# PATHS_1_2_SMD.net
KiCad netlist of a schematic drawn in EAGLE
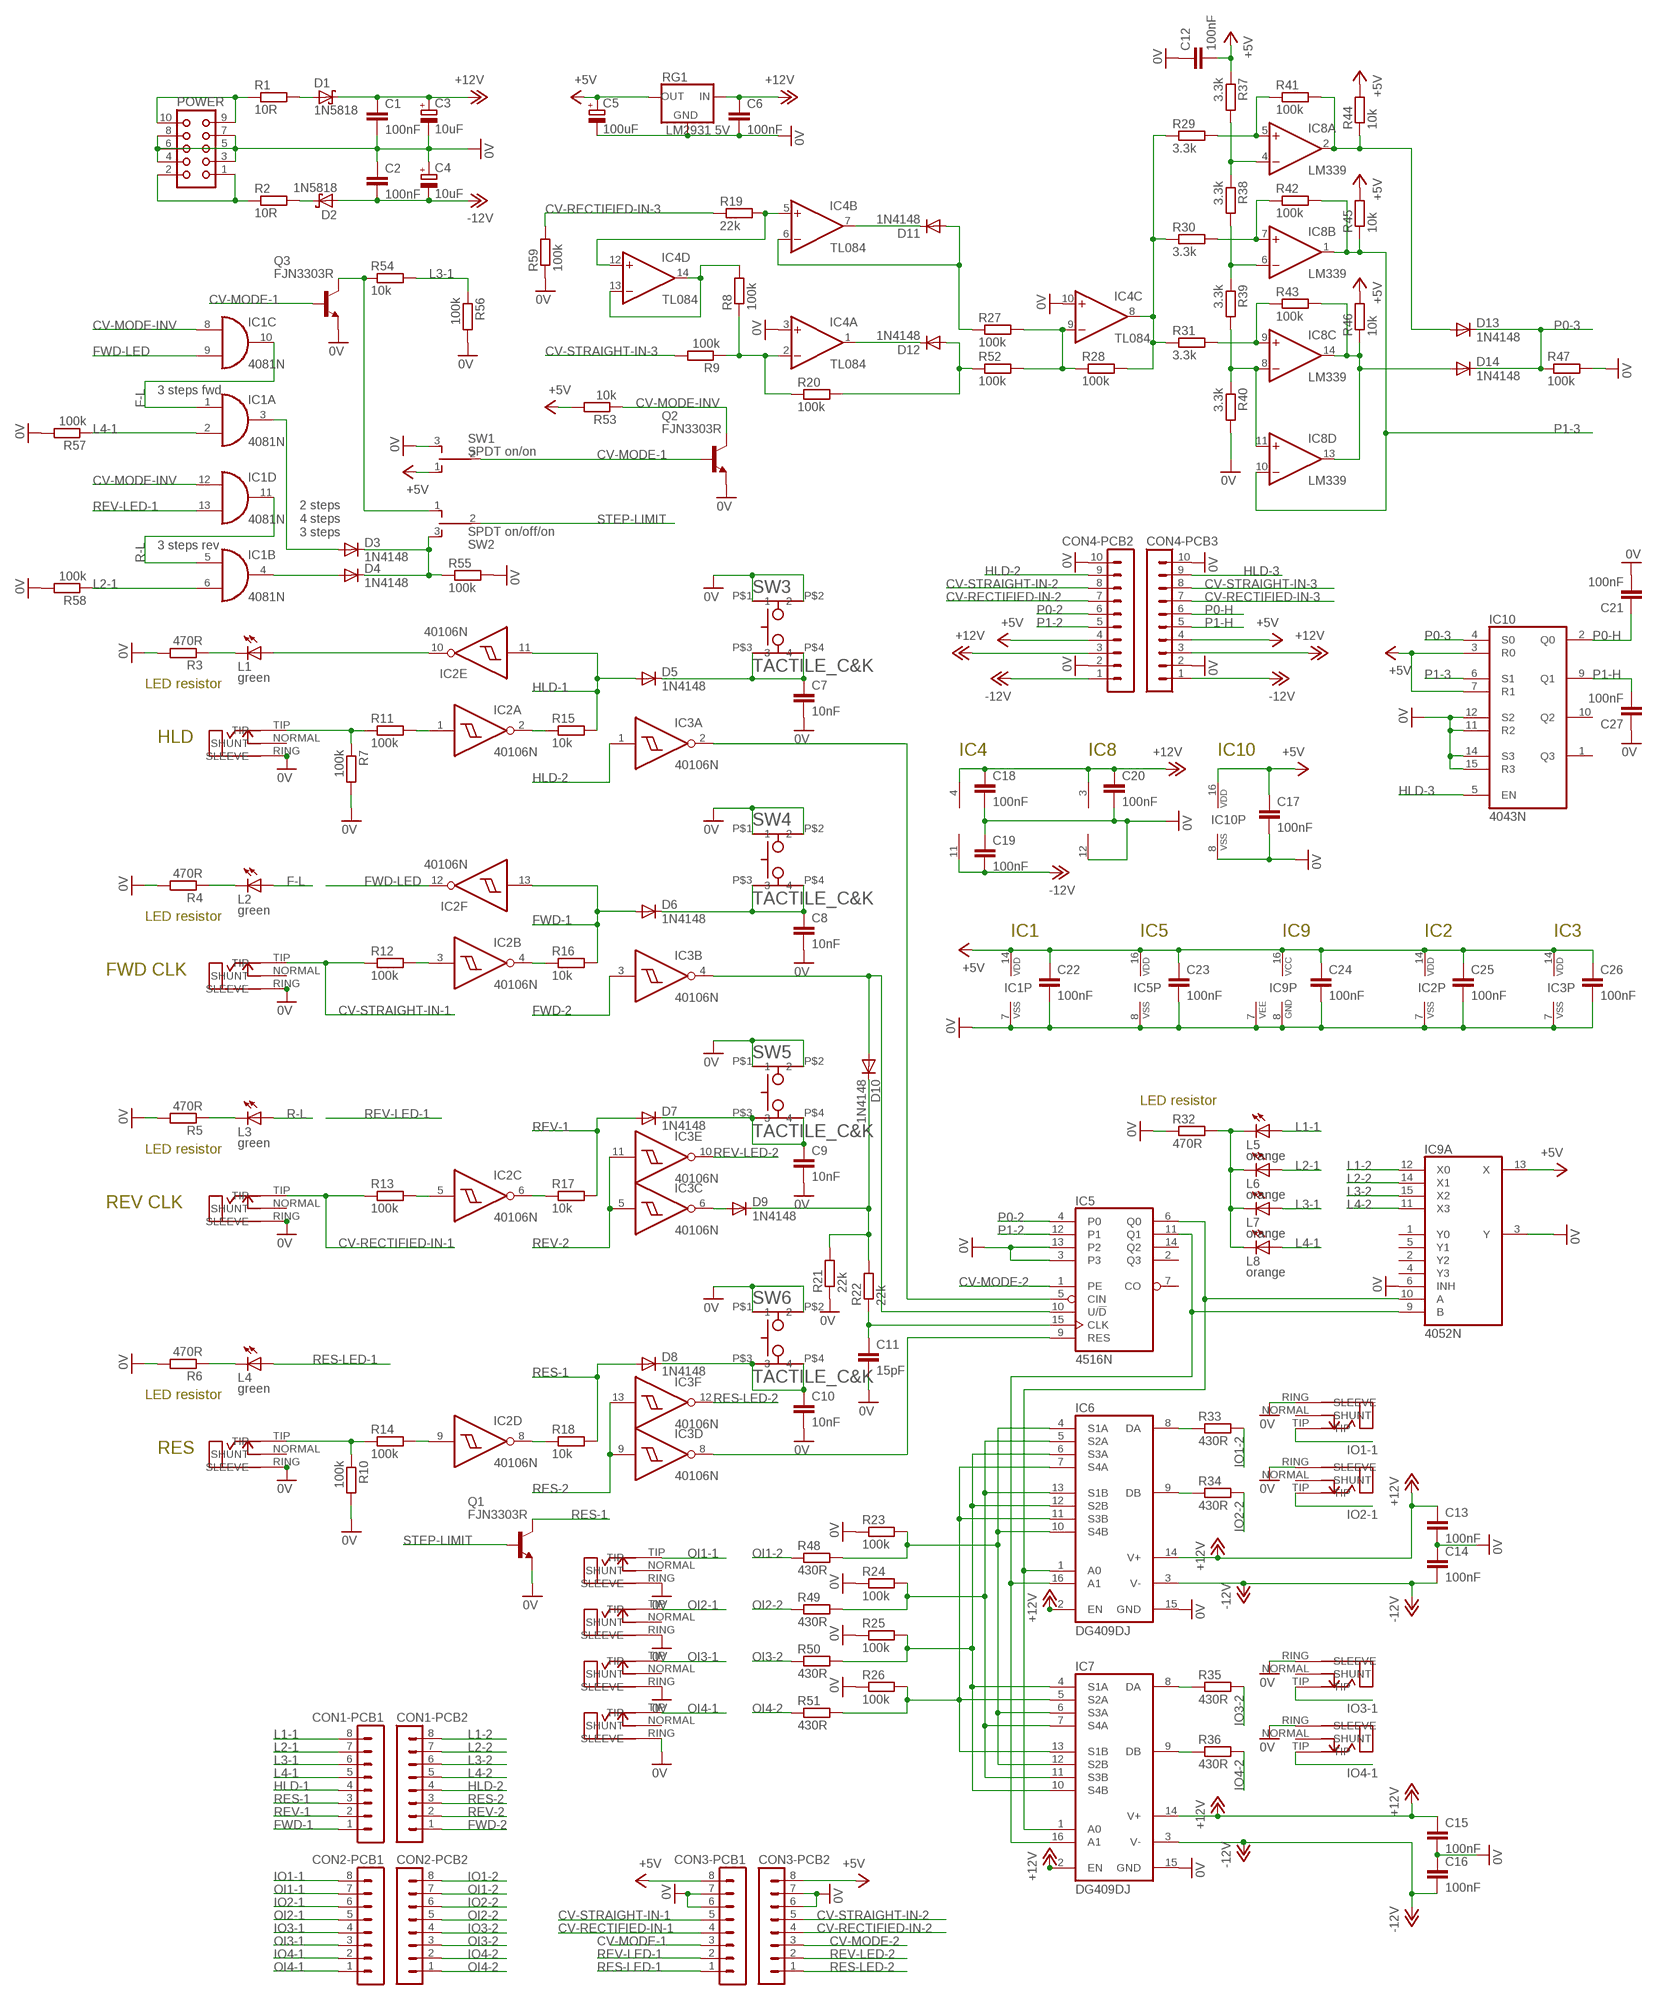
[diagram p0: schematic, sheet 1]

(export (version "E")
  (design (tool "Eeschema 10.0.6"))
  (components
    (comp (ref "C1")
      (value "100nF")
      (footprint "eagle-import:C025-024X044")
      (libsource (lib "eagle-import") (part "C-EU025-024X044"))
    )
    (comp (ref "C2")
      (value "100nF")
      (footprint "eagle-import:C025-024X044")
      (libsource (lib "eagle-import") (part "C-EU025-024X044"))
    )
    (comp (ref "C3")
      (value "10uF")
      (footprint "eagle-import:E2-5")
      (libsource (lib "eagle-import") (part "CPOL-EUE2-5"))
    )
    (comp (ref "C4")
      (value "10uF")
      (footprint "eagle-import:E2-5")
      (libsource (lib "eagle-import") (part "CPOL-EUE2-5"))
    )
    (comp (ref "C5")
      (value "100uF")
      (footprint "eagle-import:E2,5-6")
      (libsource (lib "eagle-import") (part "CPOL-EUE2.5-6"))
    )
    (comp (ref "C6")
      (value "100nF")
      (footprint "eagle-import:C025-024X044")
      (libsource (lib "eagle-import") (part "C-EU025-024X044"))
    )
    (comp (ref "C7")
      (value "10nF")
      (footprint "eagle-import:C025-024X044")
      (libsource (lib "eagle-import") (part "C-EU025-024X044"))
    )
    (comp (ref "C8")
      (value "10nF")
      (footprint "eagle-import:C025-024X044")
      (libsource (lib "eagle-import") (part "C-EU025-024X044"))
    )
    (comp (ref "C9")
      (value "10nF")
      (footprint "eagle-import:C025-024X044")
      (libsource (lib "eagle-import") (part "C-EU025-024X044"))
    )
    (comp (ref "C10")
      (value "10nF")
      (footprint "eagle-import:C025-024X044")
      (libsource (lib "eagle-import") (part "C-EU025-024X044"))
    )
    (comp (ref "C11")
      (value "15pF")
      (footprint "eagle-import:C025-024X044")
      (libsource (lib "eagle-import") (part "C-EU025-024X044"))
    )
    (comp (ref "C12")
      (value "100nF")
      (footprint "eagle-import:C025-024X044")
      (libsource (lib "eagle-import") (part "C-EU025-024X044"))
    )
    (comp (ref "C13")
      (value "100nF")
      (footprint "eagle-import:C025-024X044")
      (libsource (lib "eagle-import") (part "C-EU025-024X044"))
    )
    (comp (ref "C14")
      (value "100nF")
      (footprint "eagle-import:C025-024X044")
      (libsource (lib "eagle-import") (part "C-EU025-024X044"))
    )
    (comp (ref "C15")
      (value "100nF")
      (footprint "eagle-import:C025-024X044")
      (libsource (lib "eagle-import") (part "C-EU025-024X044"))
    )
    (comp (ref "C16")
      (value "100nF")
      (footprint "eagle-import:C025-024X044")
      (libsource (lib "eagle-import") (part "C-EU025-024X044"))
    )
    (comp (ref "C17")
      (value "100nF")
      (footprint "eagle-import:C025-024X044")
      (libsource (lib "eagle-import") (part "C-EU025-024X044"))
    )
    (comp (ref "C18")
      (value "100nF")
      (footprint "eagle-import:C025-024X044")
      (libsource (lib "eagle-import") (part "C-EU025-024X044"))
    )
    (comp (ref "C19")
      (value "100nF")
      (footprint "eagle-import:C025-024X044")
      (libsource (lib "eagle-import") (part "C-EU025-024X044"))
    )
    (comp (ref "C20")
      (value "100nF")
      (footprint "eagle-import:C025-024X044")
      (libsource (lib "eagle-import") (part "C-EU025-024X044"))
    )
    (comp (ref "C21")
      (value "100nF")
      (footprint "eagle-import:C025-024X044")
      (libsource (lib "eagle-import") (part "C-EU025-024X044"))
    )
    (comp (ref "C22")
      (value "100nF")
      (footprint "eagle-import:C025-024X044")
      (libsource (lib "eagle-import") (part "C-EU025-024X044"))
    )
    (comp (ref "C23")
      (value "100nF")
      (footprint "eagle-import:C025-024X044")
      (libsource (lib "eagle-import") (part "C-EU025-024X044"))
    )
    (comp (ref "C24")
      (value "100nF")
      (footprint "eagle-import:C025-024X044")
      (libsource (lib "eagle-import") (part "C-EU025-024X044"))
    )
    (comp (ref "C25")
      (value "100nF")
      (footprint "eagle-import:C025-024X044")
      (libsource (lib "eagle-import") (part "C-EU025-024X044"))
    )
    (comp (ref "C26")
      (value "100nF")
      (footprint "eagle-import:C025-024X044")
      (libsource (lib "eagle-import") (part "C-EU025-024X044"))
    )
    (comp (ref "C27")
      (value "100nF")
      (footprint "eagle-import:C025-024X044")
      (libsource (lib "eagle-import") (part "C-EU025-024X044"))
    )
    (comp (ref "CON1-PCB1")
      (value "MA08-1")
      (footprint "eagle-import:MA08-1")
      (libsource (lib "eagle-import") (part "MA08-1"))
    )
    (comp (ref "CON1-PCB2")
      (value "MA08-1")
      (footprint "eagle-import:MA08-1")
      (libsource (lib "eagle-import") (part "MA08-1"))
    )
    (comp (ref "CON2-PCB1")
      (value "MA08-1")
      (footprint "eagle-import:MA08-1")
      (libsource (lib "eagle-import") (part "MA08-1"))
    )
    (comp (ref "CON2-PCB2")
      (value "MA08-1")
      (footprint "eagle-import:MA08-1")
      (libsource (lib "eagle-import") (part "MA08-1"))
    )
    (comp (ref "CON3-PCB1")
      (value "MA08-1")
      (footprint "eagle-import:MA08-1")
      (libsource (lib "eagle-import") (part "MA08-1"))
    )
    (comp (ref "CON3-PCB2")
      (value "MA08-1")
      (footprint "eagle-import:MA08-1")
      (libsource (lib "eagle-import") (part "MA08-1"))
    )
    (comp (ref "CON4-PCB2")
      (value "MA10-1")
      (footprint "eagle-import:MA10-1")
      (libsource (lib "eagle-import") (part "MA10-1"))
    )
    (comp (ref "CON4-PCB3")
      (value "MA10-1")
      (footprint "eagle-import:MA10-1")
      (libsource (lib "eagle-import") (part "MA10-1"))
    )
    (comp (ref "D1")
      (value "1N5818")
      (footprint "eagle-import:DO41-7")
      (libsource (lib "eagle-import") (part "SB130DO-204AL"))
    )
    (comp (ref "D2")
      (value "1N5818")
      (footprint "eagle-import:DO41-7")
      (libsource (lib "eagle-import") (part "SB130DO-204AL"))
    )
    (comp (ref "D3")
      (value "1N4148")
      (footprint "eagle-import:DO35-6")
      (libsource (lib "eagle-import") (part "1N4148DO35-6"))
    )
    (comp (ref "D4")
      (value "1N4148")
      (footprint "eagle-import:DO35-6")
      (libsource (lib "eagle-import") (part "1N4148DO35-6"))
    )
    (comp (ref "D5")
      (value "1N4148")
      (footprint "eagle-import:DO35-6")
      (libsource (lib "eagle-import") (part "1N4148DO35-6"))
    )
    (comp (ref "D6")
      (value "1N4148")
      (footprint "eagle-import:DO35-6")
      (libsource (lib "eagle-import") (part "1N4148DO35-6"))
    )
    (comp (ref "D7")
      (value "1N4148")
      (footprint "eagle-import:DO35-6")
      (libsource (lib "eagle-import") (part "1N4148DO35-6"))
    )
    (comp (ref "D8")
      (value "1N4148")
      (footprint "eagle-import:DO35-6")
      (libsource (lib "eagle-import") (part "1N4148DO35-6"))
    )
    (comp (ref "D9")
      (value "1N4148")
      (footprint "eagle-import:DO35-6")
      (libsource (lib "eagle-import") (part "1N4148DO35-6"))
    )
    (comp (ref "D10")
      (value "1N4148")
      (footprint "eagle-import:DO35-6")
      (libsource (lib "eagle-import") (part "1N4148DO35-6"))
    )
    (comp (ref "D11")
      (value "1N4148")
      (footprint "eagle-import:DO35-6")
      (libsource (lib "eagle-import") (part "1N4148DO35-6"))
    )
    (comp (ref "D12")
      (value "1N4148")
      (footprint "eagle-import:DO35-6")
      (libsource (lib "eagle-import") (part "1N4148DO35-6"))
    )
    (comp (ref "D13")
      (value "1N4148")
      (footprint "eagle-import:DO35-6")
      (libsource (lib "eagle-import") (part "1N4148DO35-6"))
    )
    (comp (ref "D14")
      (value "1N4148")
      (footprint "eagle-import:DO35-6")
      (libsource (lib "eagle-import") (part "1N4148DO35-6"))
    )
    (comp (ref "FWD")
      (value "ERTHENVAR_3.5MM_JACKINLINE2")
      (footprint "eagle-import:THONKICON-TWISTED")
      (libsource (lib "eagle-import") (part "ERTHENVAR_3.5MM_JACKINLINE2"))
    )
    (comp (ref "HLD")
      (value "ERTHENVAR_3.5MM_JACKINLINE2")
      (footprint "eagle-import:THONKICON-TWISTED")
      (libsource (lib "eagle-import") (part "ERTHENVAR_3.5MM_JACKINLINE2"))
    )
    (comp (ref "I/O1")
      (value "ERTHENVAR_3.5MM_JACKINLINE2")
      (footprint "eagle-import:THONKICON-TWISTED")
      (libsource (lib "eagle-import") (part "ERTHENVAR_3.5MM_JACKINLINE2"))
    )
    (comp (ref "I/O2")
      (value "ERTHENVAR_3.5MM_JACKINLINE2")
      (footprint "eagle-import:THONKICON-TWISTED")
      (libsource (lib "eagle-import") (part "ERTHENVAR_3.5MM_JACKINLINE2"))
    )
    (comp (ref "I/O3")
      (value "ERTHENVAR_3.5MM_JACKINLINE2")
      (footprint "eagle-import:THONKICON-TWISTED")
      (libsource (lib "eagle-import") (part "ERTHENVAR_3.5MM_JACKINLINE2"))
    )
    (comp (ref "I/O4")
      (value "ERTHENVAR_3.5MM_JACKINLINE2")
      (footprint "eagle-import:THONKICON-TWISTED")
      (libsource (lib "eagle-import") (part "ERTHENVAR_3.5MM_JACKINLINE2"))
    )
    (comp (ref "IC1")
      (value "4081N")
      (footprint "eagle-import:DIL14")
      (libsource (lib "eagle-import") (part "4081N"))
    )
    (comp (ref "IC2")
      (value "40106N")
      (footprint "eagle-import:DIL14")
      (libsource (lib "eagle-import") (part "40106N"))
    )
    (comp (ref "IC3")
      (value "40106N")
      (footprint "eagle-import:DIL14")
      (libsource (lib "eagle-import") (part "40106N"))
    )
    (comp (ref "IC4")
      (value "TL084")
      (footprint "eagle-import:DIL14")
      (libsource (lib "eagle-import") (part "TL074P"))
    )
    (comp (ref "IC5")
      (value "4516N")
      (footprint "eagle-import:DIL16")
      (libsource (lib "eagle-import") (part "4516N"))
    )
    (comp (ref "IC6")
      (value "DG409DJ")
      (footprint "eagle-import:DIL16")
      (fields (field (name "MF") "INTERSIL"))
      (libsource (lib "eagle-import") (part "DG409DJ"))
    )
    (comp (ref "IC7")
      (value "DG409DJ")
      (footprint "eagle-import:DIL16")
      (fields (field (name "MF") "INTERSIL"))
      (libsource (lib "eagle-import") (part "DG409DJ"))
    )
    (comp (ref "IC8")
      (value "LM339")
      (footprint "eagle-import:DIL14")
      (libsource (lib "eagle-import") (part "LM2901N"))
    )
    (comp (ref "IC9")
      (value "4052N")
      (footprint "eagle-import:DIL16")
      (libsource (lib "eagle-import") (part "4052N"))
    )
    (comp (ref "IC10")
      (value "4043N")
      (footprint "eagle-import:DIL16")
      (libsource (lib "eagle-import") (part "4043N"))
    )
    (comp (ref "L1")
      (value "green")
      (footprint "eagle-import:LED3MM")
      (libsource (lib "eagle-import") (part "LED3MM"))
    )
    (comp (ref "L2")
      (value "green")
      (footprint "eagle-import:LED3MM")
      (libsource (lib "eagle-import") (part "LED3MM"))
    )
    (comp (ref "L3")
      (value "green")
      (footprint "eagle-import:LED3MM")
      (libsource (lib "eagle-import") (part "LED3MM"))
    )
    (comp (ref "L4")
      (value "green")
      (footprint "eagle-import:LED3MM")
      (libsource (lib "eagle-import") (part "LED3MM"))
    )
    (comp (ref "L5")
      (value "orange")
      (footprint "eagle-import:LED3MM")
      (libsource (lib "eagle-import") (part "LED3MM"))
    )
    (comp (ref "L6")
      (value "orange")
      (footprint "eagle-import:LED3MM")
      (libsource (lib "eagle-import") (part "LED3MM"))
    )
    (comp (ref "L7")
      (value "orange")
      (footprint "eagle-import:LED3MM")
      (libsource (lib "eagle-import") (part "LED3MM"))
    )
    (comp (ref "L8")
      (value "orange")
      (footprint "eagle-import:LED3MM")
      (libsource (lib "eagle-import") (part "LED3MM"))
    )
    (comp (ref "O/I1")
      (value "ERTHENVAR_3.5MM_JACKINLINE2")
      (footprint "eagle-import:THONKICON-TWISTED")
      (libsource (lib "eagle-import") (part "ERTHENVAR_3.5MM_JACKINLINE2"))
    )
    (comp (ref "O/I2")
      (value "ERTHENVAR_3.5MM_JACKINLINE2")
      (footprint "eagle-import:THONKICON-TWISTED")
      (libsource (lib "eagle-import") (part "ERTHENVAR_3.5MM_JACKINLINE2"))
    )
    (comp (ref "O/I3")
      (value "ERTHENVAR_3.5MM_JACKINLINE2")
      (footprint "eagle-import:THONKICON-TWISTED")
      (libsource (lib "eagle-import") (part "ERTHENVAR_3.5MM_JACKINLINE2"))
    )
    (comp (ref "O/I4")
      (value "ERTHENVAR_3.5MM_JACKINLINE2")
      (footprint "eagle-import:THONKICON-TWISTED")
      (libsource (lib "eagle-import") (part "ERTHENVAR_3.5MM_JACKINLINE2"))
    )
    (comp (ref "POWER")
      (value "CON10L")
      (footprint "eagle-import:CON10L")
      (libsource (lib "eagle-import") (part "CON10L"))
    )
    (comp (ref "Q1")
      (value "FJN3303R")
      (footprint "eagle-import:TO92-LINE")
      (libsource (lib "eagle-import") (part "FJN3303R"))
    )
    (comp (ref "Q2")
      (value "FJN3303R")
      (footprint "eagle-import:TO92-LINE")
      (libsource (lib "eagle-import") (part "FJN3303R"))
    )
    (comp (ref "Q3")
      (value "FJN3303R")
      (footprint "eagle-import:TO92-LINE")
      (libsource (lib "eagle-import") (part "FJN3303R"))
    )
    (comp (ref "R1")
      (value "10R")
      (footprint "eagle-import:0207_9")
      (libsource (lib "eagle-import") (part "R-EU_0207/10"))
    )
    (comp (ref "R2")
      (value "10R")
      (footprint "eagle-import:0207_9")
      (libsource (lib "eagle-import") (part "R-EU_0207/10"))
    )
    (comp (ref "R3")
      (value "470R")
      (footprint "eagle-import:0204_5")
      (libsource (lib "eagle-import") (part "R-EU_0204/5"))
    )
    (comp (ref "R4")
      (value "470R")
      (footprint "eagle-import:0204_5")
      (libsource (lib "eagle-import") (part "R-EU_0204/5"))
    )
    (comp (ref "R5")
      (value "470R")
      (footprint "eagle-import:0204_5")
      (libsource (lib "eagle-import") (part "R-EU_0204/5"))
    )
    (comp (ref "R6")
      (value "470R")
      (footprint "eagle-import:0204_5")
      (libsource (lib "eagle-import") (part "R-EU_0204/5"))
    )
    (comp (ref "R7")
      (value "100k")
      (footprint "eagle-import:0204_5")
      (libsource (lib "eagle-import") (part "R-EU_0204/5"))
    )
    (comp (ref "R8")
      (value "100k")
      (footprint "eagle-import:0204_5")
      (libsource (lib "eagle-import") (part "R-EU_0204/5"))
    )
    (comp (ref "R9")
      (value "100k")
      (footprint "eagle-import:0204_5")
      (libsource (lib "eagle-import") (part "R-EU_0204/5"))
    )
    (comp (ref "R10")
      (value "100k")
      (footprint "eagle-import:0204_5")
      (libsource (lib "eagle-import") (part "R-EU_0204/5"))
    )
    (comp (ref "R11")
      (value "100k")
      (footprint "eagle-import:0204_5")
      (libsource (lib "eagle-import") (part "R-EU_0204/5"))
    )
    (comp (ref "R12")
      (value "100k")
      (footprint "eagle-import:0204_5")
      (libsource (lib "eagle-import") (part "R-EU_0204/5"))
    )
    (comp (ref "R13")
      (value "100k")
      (footprint "eagle-import:0204_5")
      (libsource (lib "eagle-import") (part "R-EU_0204/5"))
    )
    (comp (ref "R14")
      (value "100k")
      (footprint "eagle-import:0204_5")
      (libsource (lib "eagle-import") (part "R-EU_0204/5"))
    )
    (comp (ref "R15")
      (value "10k")
      (footprint "eagle-import:0204_5")
      (libsource (lib "eagle-import") (part "R-EU_0204/5"))
    )
    (comp (ref "R16")
      (value "10k")
      (footprint "eagle-import:0204_5")
      (libsource (lib "eagle-import") (part "R-EU_0204/5"))
    )
    (comp (ref "R17")
      (value "10k")
      (footprint "eagle-import:0204_5")
      (libsource (lib "eagle-import") (part "R-EU_0204/5"))
    )
    (comp (ref "R18")
      (value "10k")
      (footprint "eagle-import:0204_5")
      (libsource (lib "eagle-import") (part "R-EU_0204/5"))
    )
    (comp (ref "R19")
      (value "22k")
      (footprint "eagle-import:0204_5")
      (libsource (lib "eagle-import") (part "R-EU_0204/5"))
    )
    (comp (ref "R20")
      (value "100k")
      (footprint "eagle-import:0204_5")
      (libsource (lib "eagle-import") (part "R-EU_0204/5"))
    )
    (comp (ref "R21")
      (value "22k")
      (footprint "eagle-import:0204_5")
      (libsource (lib "eagle-import") (part "R-EU_0204/5"))
    )
    (comp (ref "R22")
      (value "22k")
      (footprint "eagle-import:0204_5")
      (libsource (lib "eagle-import") (part "R-EU_0204/5"))
    )
    (comp (ref "R23")
      (value "100k")
      (footprint "eagle-import:0204_5")
      (libsource (lib "eagle-import") (part "R-EU_0204/5"))
    )
    (comp (ref "R24")
      (value "100k")
      (footprint "eagle-import:0204_5")
      (libsource (lib "eagle-import") (part "R-EU_0204/5"))
    )
    (comp (ref "R25")
      (value "100k")
      (footprint "eagle-import:0204_5")
      (libsource (lib "eagle-import") (part "R-EU_0204/5"))
    )
    (comp (ref "R26")
      (value "100k")
      (footprint "eagle-import:0204_5")
      (libsource (lib "eagle-import") (part "R-EU_0204/5"))
    )
    (comp (ref "R27")
      (value "100k")
      (footprint "eagle-import:0204_5")
      (libsource (lib "eagle-import") (part "R-EU_0204/5"))
    )
    (comp (ref "R28")
      (value "100k")
      (footprint "eagle-import:0204_5")
      (libsource (lib "eagle-import") (part "R-EU_0204/5"))
    )
    (comp (ref "R29")
      (value "3.3k")
      (footprint "eagle-import:0204_5")
      (libsource (lib "eagle-import") (part "R-EU_0204/5"))
    )
    (comp (ref "R30")
      (value "3.3k")
      (footprint "eagle-import:0204_5")
      (libsource (lib "eagle-import") (part "R-EU_0204/5"))
    )
    (comp (ref "R31")
      (value "3.3k")
      (footprint "eagle-import:0204_5")
      (libsource (lib "eagle-import") (part "R-EU_0204/5"))
    )
    (comp (ref "R32")
      (value "470R")
      (footprint "eagle-import:0204_5")
      (libsource (lib "eagle-import") (part "R-EU_0204/5"))
    )
    (comp (ref "R33")
      (value "430R")
      (footprint "eagle-import:0207_9")
      (libsource (lib "eagle-import") (part "R-EU_0207/10"))
    )
    (comp (ref "R34")
      (value "430R")
      (footprint "eagle-import:0207_9")
      (libsource (lib "eagle-import") (part "R-EU_0207/10"))
    )
    (comp (ref "R35")
      (value "430R")
      (footprint "eagle-import:0207_9")
      (libsource (lib "eagle-import") (part "R-EU_0207/10"))
    )
    (comp (ref "R36")
      (value "430R")
      (footprint "eagle-import:0207_9")
      (libsource (lib "eagle-import") (part "R-EU_0207/10"))
    )
    (comp (ref "R37")
      (value "3.3k")
      (footprint "eagle-import:0204_5")
      (libsource (lib "eagle-import") (part "R-EU_0204/5"))
    )
    (comp (ref "R38")
      (value "3.3k")
      (footprint "eagle-import:0204_5")
      (libsource (lib "eagle-import") (part "R-EU_0204/5"))
    )
    (comp (ref "R39")
      (value "3.3k")
      (footprint "eagle-import:0204_5")
      (libsource (lib "eagle-import") (part "R-EU_0204/5"))
    )
    (comp (ref "R40")
      (value "3.3k")
      (footprint "eagle-import:0204_5")
      (libsource (lib "eagle-import") (part "R-EU_0204/5"))
    )
    (comp (ref "R41")
      (value "100k")
      (footprint "eagle-import:0204_5")
      (libsource (lib "eagle-import") (part "R-EU_0204/5"))
    )
    (comp (ref "R42")
      (value "100k")
      (footprint "eagle-import:0204_5")
      (libsource (lib "eagle-import") (part "R-EU_0204/5"))
    )
    (comp (ref "R43")
      (value "100k")
      (footprint "eagle-import:0204_5")
      (libsource (lib "eagle-import") (part "R-EU_0204/5"))
    )
    (comp (ref "R44")
      (value "10k")
      (footprint "eagle-import:0204_5")
      (libsource (lib "eagle-import") (part "R-EU_0204/5"))
    )
    (comp (ref "R45")
      (value "10k")
      (footprint "eagle-import:0204_5")
      (libsource (lib "eagle-import") (part "R-EU_0204/5"))
    )
    (comp (ref "R46")
      (value "10k")
      (footprint "eagle-import:0204_5")
      (libsource (lib "eagle-import") (part "R-EU_0204/5"))
    )
    (comp (ref "R47")
      (value "100k")
      (footprint "eagle-import:0204_5")
      (libsource (lib "eagle-import") (part "R-EU_0204/5"))
    )
    (comp (ref "R48")
      (value "430R")
      (footprint "eagle-import:0207_9")
      (libsource (lib "eagle-import") (part "R-EU_0207/10"))
    )
    (comp (ref "R49")
      (value "430R")
      (footprint "eagle-import:0207_9")
      (libsource (lib "eagle-import") (part "R-EU_0207/10"))
    )
    (comp (ref "R50")
      (value "430R")
      (footprint "eagle-import:0207_9")
      (libsource (lib "eagle-import") (part "R-EU_0207/10"))
    )
    (comp (ref "R51")
      (value "430R")
      (footprint "eagle-import:0207_9")
      (libsource (lib "eagle-import") (part "R-EU_0207/10"))
    )
    (comp (ref "R52")
      (value "100k")
      (footprint "eagle-import:0204_5")
      (libsource (lib "eagle-import") (part "R-EU_0204/5"))
    )
    (comp (ref "R53")
      (value "10k")
      (footprint "eagle-import:0204_5")
      (libsource (lib "eagle-import") (part "R-EU_0204/5"))
    )
    (comp (ref "R54")
      (value "10k")
      (footprint "eagle-import:0204_5")
      (libsource (lib "eagle-import") (part "R-EU_0204/5"))
    )
    (comp (ref "R55")
      (value "100k")
      (footprint "eagle-import:0204_5")
      (libsource (lib "eagle-import") (part "R-EU_0204/5"))
    )
    (comp (ref "R56")
      (value "100k")
      (footprint "eagle-import:0204_5")
      (libsource (lib "eagle-import") (part "R-EU_0204/5"))
    )
    (comp (ref "R57")
      (value "100k")
      (footprint "eagle-import:0204_5")
      (libsource (lib "eagle-import") (part "R-EU_0204/5"))
    )
    (comp (ref "R58")
      (value "100k")
      (footprint "eagle-import:0204_5")
      (libsource (lib "eagle-import") (part "R-EU_0204/5"))
    )
    (comp (ref "R59")
      (value "100k")
      (footprint "eagle-import:0204_5")
      (libsource (lib "eagle-import") (part "R-EU_0204/5"))
    )
    (comp (ref "RES")
      (value "ERTHENVAR_3.5MM_JACKINLINE2")
      (footprint "eagle-import:THONKICON-TWISTED")
      (libsource (lib "eagle-import") (part "ERTHENVAR_3.5MM_JACKINLINE2"))
    )
    (comp (ref "REV")
      (value "ERTHENVAR_3.5MM_JACKINLINE2")
      (footprint "eagle-import:THONKICON-TWISTED")
      (libsource (lib "eagle-import") (part "ERTHENVAR_3.5MM_JACKINLINE2"))
    )
    (comp (ref "RG1")
      (value "LM2931 5V")
      (footprint "eagle-import:TO92-LINE")
      (libsource (lib "eagle-import") (part "78LXXLM2931XXX"))
    )
    (comp (ref "SW1")
      (value "SPDT on/on")
      (footprint "eagle-import:SPDT-HORIZONTAL-TOP-SUBMINI-MULTICOMP")
      (libsource (lib "eagle-import") (part "SPDTTOP-SUBMINI"))
    )
    (comp (ref "SW2")
      (value "SPDT on/off/on")
      (footprint "eagle-import:SPDT-HORIZONTAL-TOP-SUBMINI-MULTICOMP")
      (libsource (lib "eagle-import") (part "SPDTTOP-SUBMINI"))
    )
    (comp (ref "SW3")
      (value "TACTILE_C&K")
      (footprint "eagle-import:TACTILE_CK")
      (libsource (lib "eagle-import") (part "TACTILE_C&K"))
    )
    (comp (ref "SW4")
      (value "TACTILE_C&K")
      (footprint "eagle-import:TACTILE_CK")
      (libsource (lib "eagle-import") (part "TACTILE_C&K"))
    )
    (comp (ref "SW5")
      (value "TACTILE_C&K")
      (footprint "eagle-import:TACTILE_CK")
      (libsource (lib "eagle-import") (part "TACTILE_C&K"))
    )
    (comp (ref "SW6")
      (value "TACTILE_C&K")
      (footprint "eagle-import:TACTILE_CK")
      (libsource (lib "eagle-import") (part "TACTILE_C&K"))
    )
  )
  (nets
    (net (code "1") (name "+5V") (class "Default")
      (node (ref "C12") (pin "2") (pinfunction "2_2") (pintype "passive"))
      (node (ref "C17") (pin "1") (pinfunction "1_1") (pintype "passive"))
      (node (ref "C22") (pin "1") (pinfunction "1_1") (pintype "passive"))
      (node (ref "C23") (pin "1") (pinfunction "1_1") (pintype "passive"))
      (node (ref "C24") (pin "1") (pinfunction "1_1") (pintype "passive"))
      (node (ref "C25") (pin "1") (pinfunction "1_1") (pintype "passive"))
      (node (ref "C26") (pin "1") (pinfunction "1_1") (pintype "passive"))
      (node (ref "C5") (pin "+") (pinfunction "+_+") (pintype "passive"))
      (node (ref "CON3-PCB1") (pin "8") (pinfunction "8_8") (pintype "passive"))
      (node (ref "CON3-PCB2") (pin "8") (pinfunction "8_8") (pintype "passive"))
      (node (ref "CON4-PCB2") (pin "4") (pinfunction "4_4") (pintype "passive"))
      (node (ref "CON4-PCB3") (pin "4") (pinfunction "4_4") (pintype "passive"))
      (node (ref "IC1") (pin "14") (pinfunction "VDD_14") (pintype "power_in"))
      (node (ref "IC10") (pin "16") (pinfunction "VDD_16") (pintype "power_in"))
      (node (ref "IC10") (pin "3") (pinfunction "R0_3") (pintype "input"))
      (node (ref "IC10") (pin "7") (pinfunction "R1_7") (pintype "input"))
      (node (ref "IC2") (pin "14") (pinfunction "VDD_14") (pintype "power_in"))
      (node (ref "IC3") (pin "14") (pinfunction "VDD_14") (pintype "power_in"))
      (node (ref "IC5") (pin "16") (pinfunction "VDD_16") (pintype "power_in"))
      (node (ref "IC9") (pin "13") (pinfunction "X_13") (pintype "bidirectional"))
      (node (ref "IC9") (pin "16") (pinfunction "VCC_16") (pintype "power_in"))
      (node (ref "R37") (pin "1") (pinfunction "1_1") (pintype "passive"))
      (node (ref "R44") (pin "2") (pinfunction "2_2") (pintype "passive"))
      (node (ref "R45") (pin "2") (pinfunction "2_2") (pintype "passive"))
      (node (ref "R46") (pin "2") (pinfunction "2_2") (pintype "passive"))
      (node (ref "R53") (pin "2") (pinfunction "2_2") (pintype "passive"))
      (node (ref "RG1") (pin "3") (pinfunction "OUT_3") (pintype "passive"))
      (node (ref "SW1") (pin "1") (pinfunction "1_1") (pintype "passive"))
    )
    (net (code "2") (name "+12V") (class "Default")
      (node (ref "C1") (pin "1") (pinfunction "1_1") (pintype "passive"))
      (node (ref "C13") (pin "1") (pinfunction "1_1") (pintype "passive"))
      (node (ref "C15") (pin "1") (pinfunction "1_1") (pintype "passive"))
      (node (ref "C18") (pin "1") (pinfunction "1_1") (pintype "passive"))
      (node (ref "C20") (pin "1") (pinfunction "1_1") (pintype "passive"))
      (node (ref "C3") (pin "+") (pinfunction "+_+") (pintype "passive"))
      (node (ref "C6") (pin "1") (pinfunction "1_1") (pintype "passive"))
      (node (ref "CON4-PCB2") (pin "3") (pinfunction "3_3") (pintype "passive"))
      (node (ref "CON4-PCB3") (pin "3") (pinfunction "3_3") (pintype "passive"))
      (node (ref "D1") (pin "C") (pinfunction "C_C") (pintype "passive"))
      (node (ref "IC4") (pin "4") (pinfunction "V+_4") (pintype "power_in"))
      (node (ref "IC6") (pin "14") (pinfunction "V+_14") (pintype "power_in"))
      (node (ref "IC6") (pin "2") (pinfunction "EN_2") (pintype "input"))
      (node (ref "IC7") (pin "14") (pinfunction "V+_14") (pintype "power_in"))
      (node (ref "IC7") (pin "2") (pinfunction "EN_2") (pintype "input"))
      (node (ref "IC8") (pin "3") (pinfunction "V+_3") (pintype "power_in"))
      (node (ref "RG1") (pin "1") (pinfunction "IN_1") (pintype "input"))
    )
    (net (code "3") (name "-12V") (class "Default")
      (node (ref "C14") (pin "2") (pinfunction "2_2") (pintype "passive"))
      (node (ref "C16") (pin "2") (pinfunction "2_2") (pintype "passive"))
      (node (ref "C19") (pin "2") (pinfunction "2_2") (pintype "passive"))
      (node (ref "C2") (pin "2") (pinfunction "2_2") (pintype "passive"))
      (node (ref "C4") (pin "-") (pinfunction "-_-") (pintype "passive"))
      (node (ref "CON4-PCB2") (pin "1") (pinfunction "1_1") (pintype "passive"))
      (node (ref "CON4-PCB3") (pin "1") (pinfunction "1_1") (pintype "passive"))
      (node (ref "D2") (pin "A") (pinfunction "A_A") (pintype "passive"))
      (node (ref "IC4") (pin "11") (pinfunction "V-_11") (pintype "power_in"))
      (node (ref "IC6") (pin "3") (pinfunction "V-_3") (pintype "power_in"))
      (node (ref "IC7") (pin "3") (pinfunction "V-_3") (pintype "power_in"))
    )
    (net (code "4") (name "/CV-MODE-1") (class "Default")
      (node (ref "CON3-PCB1") (pin "3") (pinfunction "3_3") (pintype "passive"))
      (node (ref "Q2") (pin "1") (pinfunction "B_1") (pintype "passive"))
      (node (ref "Q3") (pin "1") (pinfunction "B_1") (pintype "passive"))
      (node (ref "SW1") (pin "2") (pinfunction "2_2") (pintype "passive"))
    )
    (net (code "5") (name "/CV-MODE-2") (class "Default")
      (node (ref "CON3-PCB2") (pin "3") (pinfunction "3_3") (pintype "passive"))
      (node (ref "IC5") (pin "1") (pinfunction "PE_1") (pintype "input"))
    )
    (net (code "6") (name "/CV-MODE-INV") (class "Default")
      (node (ref "IC1") (pin "12") (pinfunction "I0_12") (pintype "input"))
      (node (ref "IC1") (pin "8") (pinfunction "I0_8") (pintype "input"))
      (node (ref "Q2") (pin "2") (pinfunction "C_2") (pintype "passive"))
      (node (ref "R53") (pin "1") (pinfunction "1_1") (pintype "passive"))
    )
    (net (code "7") (name "/CV-RECTIFIED-IN-1") (class "Default")
      (node (ref "CON3-PCB1") (pin "4") (pinfunction "4_4") (pintype "passive"))
      (node (ref "R13") (pin "1") (pinfunction "1_1") (pintype "passive"))
      (node (ref "REV") (pin "TIP") (pinfunction "TIP_TIP") (pintype "bidirectional"))
    )
    (net (code "8") (name "/CV-RECTIFIED-IN-2") (class "Default")
      (node (ref "CON3-PCB2") (pin "4") (pinfunction "4_4") (pintype "passive"))
      (node (ref "CON4-PCB2") (pin "7") (pinfunction "7_7") (pintype "passive"))
    )
    (net (code "9") (name "/CV-RECTIFIED-IN-3") (class "Default")
      (node (ref "CON4-PCB3") (pin "7") (pinfunction "7_7") (pintype "passive"))
      (node (ref "R19") (pin "1") (pinfunction "1_1") (pintype "passive"))
      (node (ref "R59") (pin "2") (pinfunction "2_2") (pintype "passive"))
    )
    (net (code "10") (name "/CV-STRAIGHT-IN-1") (class "Default")
      (node (ref "CON3-PCB1") (pin "5") (pinfunction "5_5") (pintype "passive"))
      (node (ref "FWD") (pin "TIP") (pinfunction "TIP_TIP") (pintype "bidirectional"))
      (node (ref "R12") (pin "1") (pinfunction "1_1") (pintype "passive"))
    )
    (net (code "11") (name "/CV-STRAIGHT-IN-2") (class "Default")
      (node (ref "CON3-PCB2") (pin "5") (pinfunction "5_5") (pintype "passive"))
      (node (ref "CON4-PCB2") (pin "8") (pinfunction "8_8") (pintype "passive"))
    )
    (net (code "12") (name "/CV-STRAIGHT-IN-3") (class "Default")
      (node (ref "CON4-PCB3") (pin "8") (pinfunction "8_8") (pintype "passive"))
      (node (ref "R9") (pin "2") (pinfunction "2_2") (pintype "passive"))
    )
    (net (code "13") (name "/F-L") (class "Default")
      (node (ref "IC1") (pin "1") (pinfunction "I0_1") (pintype "input"))
      (node (ref "IC1") (pin "10") (pinfunction "O_10") (pintype "output"))
      (node (ref "L2") (pin "A") (pinfunction "A_A") (pintype "passive"))
    )
    (net (code "14") (name "/FWD-1") (class "Default")
      (node (ref "CON1-PCB1") (pin "1") (pinfunction "1_1") (pintype "passive"))
      (node (ref "D6") (pin "ANODE") (pinfunction "A_ANODE") (pintype "passive"))
      (node (ref "IC2") (pin "13") (pinfunction "I_13") (pintype "input"))
      (node (ref "R16") (pin "2") (pinfunction "2_2") (pintype "passive"))
    )
    (net (code "15") (name "/FWD-2") (class "Default")
      (node (ref "CON1-PCB2") (pin "1") (pinfunction "1_1") (pintype "passive"))
      (node (ref "IC3") (pin "3") (pinfunction "I_3") (pintype "input"))
    )
    (net (code "16") (name "/FWD-LED") (class "Default")
      (node (ref "IC1") (pin "9") (pinfunction "I1_9") (pintype "input"))
      (node (ref "IC2") (pin "12") (pinfunction "O_12") (pintype "output"))
    )
    (net (code "17") (name "/HLD-1") (class "Default")
      (node (ref "CON1-PCB1") (pin "4") (pinfunction "4_4") (pintype "passive"))
      (node (ref "D5") (pin "ANODE") (pinfunction "A_ANODE") (pintype "passive"))
      (node (ref "IC2") (pin "11") (pinfunction "I_11") (pintype "input"))
      (node (ref "R15") (pin "2") (pinfunction "2_2") (pintype "passive"))
    )
    (net (code "18") (name "/HLD-2") (class "Default")
      (node (ref "CON1-PCB2") (pin "4") (pinfunction "4_4") (pintype "passive"))
      (node (ref "CON4-PCB2") (pin "9") (pinfunction "9_9") (pintype "passive"))
      (node (ref "IC3") (pin "1") (pinfunction "I_1") (pintype "input"))
    )
    (net (code "19") (name "/HLD-3") (class "Default")
      (node (ref "CON4-PCB3") (pin "9") (pinfunction "9_9") (pintype "passive"))
      (node (ref "IC10") (pin "5") (pinfunction "EN_5") (pintype "input"))
    )
    (net (code "20") (name "/IO1-1") (class "Default")
      (node (ref "CON2-PCB1") (pin "8") (pinfunction "8_8") (pintype "passive"))
      (node (ref "I/O1") (pin "TIP") (pinfunction "TIP_TIP") (pintype "bidirectional"))
    )
    (net (code "21") (name "/IO1-2") (class "Default")
      (node (ref "CON2-PCB2") (pin "8") (pinfunction "8_8") (pintype "passive"))
      (node (ref "R33") (pin "2") (pinfunction "2_2") (pintype "passive"))
    )
    (net (code "22") (name "/IO2-1") (class "Default")
      (node (ref "CON2-PCB1") (pin "6") (pinfunction "6_6") (pintype "passive"))
      (node (ref "I/O2") (pin "TIP") (pinfunction "TIP_TIP") (pintype "bidirectional"))
    )
    (net (code "23") (name "/IO2-2") (class "Default")
      (node (ref "CON2-PCB2") (pin "6") (pinfunction "6_6") (pintype "passive"))
      (node (ref "R34") (pin "2") (pinfunction "2_2") (pintype "passive"))
    )
    (net (code "24") (name "/IO3-1") (class "Default")
      (node (ref "CON2-PCB1") (pin "4") (pinfunction "4_4") (pintype "passive"))
      (node (ref "I/O3") (pin "TIP") (pinfunction "TIP_TIP") (pintype "bidirectional"))
    )
    (net (code "25") (name "/IO3-2") (class "Default")
      (node (ref "CON2-PCB2") (pin "4") (pinfunction "4_4") (pintype "passive"))
      (node (ref "R35") (pin "2") (pinfunction "2_2") (pintype "passive"))
    )
    (net (code "26") (name "/IO4-1") (class "Default")
      (node (ref "CON2-PCB1") (pin "2") (pinfunction "2_2") (pintype "passive"))
      (node (ref "I/O4") (pin "TIP") (pinfunction "TIP_TIP") (pintype "bidirectional"))
    )
    (net (code "27") (name "/IO4-2") (class "Default")
      (node (ref "CON2-PCB2") (pin "2") (pinfunction "2_2") (pintype "passive"))
      (node (ref "R36") (pin "2") (pinfunction "2_2") (pintype "passive"))
    )
    (net (code "28") (name "/L1-1") (class "Default")
      (node (ref "CON1-PCB1") (pin "8") (pinfunction "8_8") (pintype "passive"))
      (node (ref "L5") (pin "A") (pinfunction "A_A") (pintype "passive"))
    )
    (net (code "29") (name "/L1-2") (class "Default")
      (node (ref "CON1-PCB2") (pin "8") (pinfunction "8_8") (pintype "passive"))
      (node (ref "IC9") (pin "12") (pinfunction "X0_12") (pintype "bidirectional"))
    )
    (net (code "30") (name "/L2-1") (class "Default")
      (node (ref "CON1-PCB1") (pin "7") (pinfunction "7_7") (pintype "passive"))
      (node (ref "IC1") (pin "6") (pinfunction "I1_6") (pintype "input"))
      (node (ref "L6") (pin "A") (pinfunction "A_A") (pintype "passive"))
      (node (ref "R58") (pin "1") (pinfunction "1_1") (pintype "passive"))
    )
    (net (code "31") (name "/L2-2") (class "Default")
      (node (ref "CON1-PCB2") (pin "7") (pinfunction "7_7") (pintype "passive"))
      (node (ref "IC9") (pin "14") (pinfunction "X1_14") (pintype "bidirectional"))
    )
    (net (code "32") (name "/L3-1") (class "Default")
      (node (ref "CON1-PCB1") (pin "6") (pinfunction "6_6") (pintype "passive"))
      (node (ref "L7") (pin "A") (pinfunction "A_A") (pintype "passive"))
      (node (ref "R54") (pin "2") (pinfunction "2_2") (pintype "passive"))
      (node (ref "R56") (pin "1") (pinfunction "1_1") (pintype "passive"))
    )
    (net (code "33") (name "/L3-2") (class "Default")
      (node (ref "CON1-PCB2") (pin "6") (pinfunction "6_6") (pintype "passive"))
      (node (ref "IC9") (pin "15") (pinfunction "X2_15") (pintype "bidirectional"))
    )
    (net (code "34") (name "/L4-1") (class "Default")
      (node (ref "CON1-PCB1") (pin "5") (pinfunction "5_5") (pintype "passive"))
      (node (ref "IC1") (pin "2") (pinfunction "I1_2") (pintype "input"))
      (node (ref "L8") (pin "A") (pinfunction "A_A") (pintype "passive"))
      (node (ref "R57") (pin "1") (pinfunction "1_1") (pintype "passive"))
    )
    (net (code "35") (name "/L4-2") (class "Default")
      (node (ref "CON1-PCB2") (pin "5") (pinfunction "5_5") (pintype "passive"))
      (node (ref "IC9") (pin "11") (pinfunction "X3_11") (pintype "bidirectional"))
    )
    (net (code "36") (name "/OI1-1") (class "Default")
      (node (ref "CON2-PCB1") (pin "7") (pinfunction "7_7") (pintype "passive"))
      (node (ref "O/I1") (pin "TIP") (pinfunction "TIP_TIP") (pintype "bidirectional"))
    )
    (net (code "37") (name "/OI1-2") (class "Default")
      (node (ref "CON2-PCB2") (pin "7") (pinfunction "7_7") (pintype "passive"))
      (node (ref "R48") (pin "1") (pinfunction "1_1") (pintype "passive"))
    )
    (net (code "38") (name "/OI2-1") (class "Default")
      (node (ref "CON2-PCB1") (pin "5") (pinfunction "5_5") (pintype "passive"))
      (node (ref "O/I2") (pin "TIP") (pinfunction "TIP_TIP") (pintype "bidirectional"))
    )
    (net (code "39") (name "/OI2-2") (class "Default")
      (node (ref "CON2-PCB2") (pin "5") (pinfunction "5_5") (pintype "passive"))
      (node (ref "R49") (pin "1") (pinfunction "1_1") (pintype "passive"))
    )
    (net (code "40") (name "/OI3-1") (class "Default")
      (node (ref "CON2-PCB1") (pin "3") (pinfunction "3_3") (pintype "passive"))
      (node (ref "O/I3") (pin "TIP") (pinfunction "TIP_TIP") (pintype "bidirectional"))
    )
    (net (code "41") (name "/OI3-2") (class "Default")
      (node (ref "CON2-PCB2") (pin "3") (pinfunction "3_3") (pintype "passive"))
      (node (ref "R50") (pin "1") (pinfunction "1_1") (pintype "passive"))
    )
    (net (code "42") (name "/OI4-1") (class "Default")
      (node (ref "CON2-PCB1") (pin "1") (pinfunction "1_1") (pintype "passive"))
      (node (ref "O/I4") (pin "TIP") (pinfunction "TIP_TIP") (pintype "bidirectional"))
    )
    (net (code "43") (name "/OI4-2") (class "Default")
      (node (ref "CON2-PCB2") (pin "1") (pinfunction "1_1") (pintype "passive"))
      (node (ref "R51") (pin "1") (pinfunction "1_1") (pintype "passive"))
    )
    (net (code "44") (name "/P0-2") (class "Default")
      (node (ref "CON4-PCB2") (pin "6") (pinfunction "6_6") (pintype "passive"))
      (node (ref "IC5") (pin "4") (pinfunction "P0_4") (pintype "input"))
    )
    (net (code "45") (name "/P0-3") (class "Default")
      (node (ref "D13") (pin "CATHODE") (pinfunction "C_CATHODE") (pintype "passive"))
      (node (ref "D14") (pin "CATHODE") (pinfunction "C_CATHODE") (pintype "passive"))
      (node (ref "IC10") (pin "4") (pinfunction "S0_4") (pintype "input"))
      (node (ref "R47") (pin "1") (pinfunction "1_1") (pintype "passive"))
    )
    (net (code "46") (name "/P0-H") (class "Default")
      (node (ref "C21") (pin "1") (pinfunction "1_1") (pintype "passive"))
      (node (ref "CON4-PCB3") (pin "6") (pinfunction "6_6") (pintype "passive"))
      (node (ref "IC10") (pin "2") (pinfunction "Q0_2") (pintype "output"))
    )
    (net (code "47") (name "/P1-2") (class "Default")
      (node (ref "CON4-PCB2") (pin "5") (pinfunction "5_5") (pintype "passive"))
      (node (ref "IC5") (pin "12") (pinfunction "P1_12") (pintype "input"))
    )
    (net (code "48") (name "/P1-3") (class "Default")
      (node (ref "IC10") (pin "6") (pinfunction "S1_6") (pintype "input"))
      (node (ref "IC8") (pin "1") (pinfunction "OUT_1") (pintype "output"))
      (node (ref "IC8") (pin "10") (pinfunction "-IN_10") (pintype "input"))
      (node (ref "R42") (pin "2") (pinfunction "2_2") (pintype "passive"))
      (node (ref "R45") (pin "1") (pinfunction "1_1") (pintype "passive"))
    )
    (net (code "49") (name "/P1-H") (class "Default")
      (node (ref "C27") (pin "2") (pinfunction "2_2") (pintype "passive"))
      (node (ref "CON4-PCB3") (pin "5") (pinfunction "5_5") (pintype "passive"))
      (node (ref "IC10") (pin "9") (pinfunction "Q1_9") (pintype "output"))
    )
    (net (code "50") (name "/R-L") (class "Default")
      (node (ref "IC1") (pin "11") (pinfunction "O_11") (pintype "output"))
      (node (ref "IC1") (pin "5") (pinfunction "I0_5") (pintype "input"))
      (node (ref "L3") (pin "A") (pinfunction "A_A") (pintype "passive"))
    )
    (net (code "51") (name "/RES-1") (class "Default")
      (node (ref "CON1-PCB1") (pin "3") (pinfunction "3_3") (pintype "passive"))
      (node (ref "D8") (pin "ANODE") (pinfunction "A_ANODE") (pintype "passive"))
      (node (ref "Q1") (pin "2") (pinfunction "C_2") (pintype "passive"))
      (node (ref "R18") (pin "2") (pinfunction "2_2") (pintype "passive"))
    )
    (net (code "52") (name "/RES-2") (class "Default")
      (node (ref "CON1-PCB2") (pin "3") (pinfunction "3_3") (pintype "passive"))
      (node (ref "IC3") (pin "13") (pinfunction "I_13") (pintype "input"))
      (node (ref "IC3") (pin "9") (pinfunction "I_9") (pintype "input"))
    )
    (net (code "53") (name "/RES-LED-1") (class "Default")
      (node (ref "CON3-PCB1") (pin "1") (pinfunction "1_1") (pintype "passive"))
      (node (ref "L4") (pin "A") (pinfunction "A_A") (pintype "passive"))
    )
    (net (code "54") (name "/RES-LED-2") (class "Default")
      (node (ref "CON3-PCB2") (pin "1") (pinfunction "1_1") (pintype "passive"))
      (node (ref "IC3") (pin "12") (pinfunction "O_12") (pintype "output"))
    )
    (net (code "55") (name "/REV-1") (class "Default")
      (node (ref "CON1-PCB1") (pin "2") (pinfunction "2_2") (pintype "passive"))
      (node (ref "D7") (pin "ANODE") (pinfunction "A_ANODE") (pintype "passive"))
      (node (ref "R17") (pin "2") (pinfunction "2_2") (pintype "passive"))
    )
    (net (code "56") (name "/REV-2") (class "Default")
      (node (ref "CON1-PCB2") (pin "2") (pinfunction "2_2") (pintype "passive"))
      (node (ref "IC3") (pin "11") (pinfunction "I_11") (pintype "input"))
      (node (ref "IC3") (pin "5") (pinfunction "I_5") (pintype "input"))
    )
    (net (code "57") (name "/REV-LED-1") (class "Default")
      (node (ref "CON3-PCB1") (pin "2") (pinfunction "2_2") (pintype "passive"))
      (node (ref "IC1") (pin "13") (pinfunction "I1_13") (pintype "input"))
    )
    (net (code "58") (name "/REV-LED-2") (class "Default")
      (node (ref "CON3-PCB2") (pin "2") (pinfunction "2_2") (pintype "passive"))
      (node (ref "IC3") (pin "10") (pinfunction "O_10") (pintype "output"))
    )
    (net (code "59") (name "/STEP-LIMIT") (class "Default")
      (node (ref "Q1") (pin "1") (pinfunction "B_1") (pintype "passive"))
      (node (ref "SW2") (pin "2") (pinfunction "2_2") (pintype "passive"))
    )
    (net (code "60") (name "0V") (class "Default")
      (node (ref "C1") (pin "2") (pinfunction "2_2") (pintype "passive"))
      (node (ref "C10") (pin "2") (pinfunction "2_2") (pintype "passive"))
      (node (ref "C11") (pin "2") (pinfunction "2_2") (pintype "passive"))
      (node (ref "C12") (pin "1") (pinfunction "1_1") (pintype "passive"))
      (node (ref "C13") (pin "2") (pinfunction "2_2") (pintype "passive"))
      (node (ref "C14") (pin "1") (pinfunction "1_1") (pintype "passive"))
      (node (ref "C15") (pin "2") (pinfunction "2_2") (pintype "passive"))
      (node (ref "C16") (pin "1") (pinfunction "1_1") (pintype "passive"))
      (node (ref "C17") (pin "2") (pinfunction "2_2") (pintype "passive"))
      (node (ref "C18") (pin "2") (pinfunction "2_2") (pintype "passive"))
      (node (ref "C19") (pin "1") (pinfunction "1_1") (pintype "passive"))
      (node (ref "C2") (pin "1") (pinfunction "1_1") (pintype "passive"))
      (node (ref "C20") (pin "2") (pinfunction "2_2") (pintype "passive"))
      (node (ref "C21") (pin "2") (pinfunction "2_2") (pintype "passive"))
      (node (ref "C22") (pin "2") (pinfunction "2_2") (pintype "passive"))
      (node (ref "C23") (pin "2") (pinfunction "2_2") (pintype "passive"))
      (node (ref "C24") (pin "2") (pinfunction "2_2") (pintype "passive"))
      (node (ref "C25") (pin "2") (pinfunction "2_2") (pintype "passive"))
      (node (ref "C26") (pin "2") (pinfunction "2_2") (pintype "passive"))
      (node (ref "C27") (pin "1") (pinfunction "1_1") (pintype "passive"))
      (node (ref "C3") (pin "-") (pinfunction "-_-") (pintype "passive"))
      (node (ref "C4") (pin "+") (pinfunction "+_+") (pintype "passive"))
      (node (ref "C5") (pin "-") (pinfunction "-_-") (pintype "passive"))
      (node (ref "C6") (pin "2") (pinfunction "2_2") (pintype "passive"))
      (node (ref "C7") (pin "2") (pinfunction "2_2") (pintype "passive"))
      (node (ref "C8") (pin "2") (pinfunction "2_2") (pintype "passive"))
      (node (ref "C9") (pin "2") (pinfunction "2_2") (pintype "passive"))
      (node (ref "CON3-PCB1") (pin "6") (pinfunction "6_6") (pintype "passive"))
      (node (ref "CON3-PCB1") (pin "7") (pinfunction "7_7") (pintype "passive"))
      (node (ref "CON3-PCB2") (pin "6") (pinfunction "6_6") (pintype "passive"))
      (node (ref "CON3-PCB2") (pin "7") (pinfunction "7_7") (pintype "passive"))
      (node (ref "CON4-PCB2") (pin "10") (pinfunction "10_10") (pintype "passive"))
      (node (ref "CON4-PCB2") (pin "2") (pinfunction "2_2") (pintype "passive"))
      (node (ref "CON4-PCB3") (pin "10") (pinfunction "10_10") (pintype "passive"))
      (node (ref "CON4-PCB3") (pin "2") (pinfunction "2_2") (pintype "passive"))
      (node (ref "FWD") (pin "RING") (pinfunction "SLEEVE_RING") (pintype "bidirectional"))
      (node (ref "HLD") (pin "RING") (pinfunction "SLEEVE_RING") (pintype "bidirectional"))
      (node (ref "I/O1") (pin "RING") (pinfunction "SLEEVE_RING") (pintype "bidirectional"))
      (node (ref "I/O2") (pin "RING") (pinfunction "SLEEVE_RING") (pintype "bidirectional"))
      (node (ref "I/O3") (pin "RING") (pinfunction "SLEEVE_RING") (pintype "bidirectional"))
      (node (ref "I/O4") (pin "RING") (pinfunction "SLEEVE_RING") (pintype "bidirectional"))
      (node (ref "IC1") (pin "7") (pinfunction "VSS_7") (pintype "power_in"))
      (node (ref "IC10") (pin "11") (pinfunction "R2_11") (pintype "input"))
      (node (ref "IC10") (pin "12") (pinfunction "S2_12") (pintype "input"))
      (node (ref "IC10") (pin "14") (pinfunction "S3_14") (pintype "input"))
      (node (ref "IC10") (pin "15") (pinfunction "R3_15") (pintype "input"))
      (node (ref "IC10") (pin "8") (pinfunction "VSS_8") (pintype "power_in"))
      (node (ref "IC2") (pin "7") (pinfunction "VSS_7") (pintype "power_in"))
      (node (ref "IC3") (pin "7") (pinfunction "VSS_7") (pintype "power_in"))
      (node (ref "IC4") (pin "10") (pinfunction "+IN_10") (pintype "input"))
      (node (ref "IC4") (pin "3") (pinfunction "+IN_3") (pintype "input"))
      (node (ref "IC5") (pin "13") (pinfunction "P2_13") (pintype "input"))
      (node (ref "IC5") (pin "3") (pinfunction "P3_3") (pintype "input"))
      (node (ref "IC5") (pin "8") (pinfunction "VSS_8") (pintype "power_in"))
      (node (ref "IC6") (pin "15") (pinfunction "GND_15") (pintype "power_in"))
      (node (ref "IC7") (pin "15") (pinfunction "GND_15") (pintype "power_in"))
      (node (ref "IC8") (pin "12") (pinfunction "V-_12") (pintype "power_in"))
      (node (ref "IC9") (pin "3") (pinfunction "Y_3") (pintype "bidirectional"))
      (node (ref "IC9") (pin "6") (pinfunction "INH_6") (pintype "input"))
      (node (ref "IC9") (pin "7") (pinfunction "VEE_7") (pintype "power_in"))
      (node (ref "IC9") (pin "8") (pinfunction "GND_8") (pintype "power_in"))
      (node (ref "O/I1") (pin "RING") (pinfunction "SLEEVE_RING") (pintype "bidirectional"))
      (node (ref "O/I2") (pin "RING") (pinfunction "SLEEVE_RING") (pintype "bidirectional"))
      (node (ref "O/I3") (pin "RING") (pinfunction "SLEEVE_RING") (pintype "bidirectional"))
      (node (ref "O/I4") (pin "RING") (pinfunction "SLEEVE_RING") (pintype "bidirectional"))
      (node (ref "POWER") (pin "3") (pinfunction "3_3") (pintype "passive"))
      (node (ref "POWER") (pin "4") (pinfunction "4_4") (pintype "passive"))
      (node (ref "POWER") (pin "5") (pinfunction "5_5") (pintype "passive"))
      (node (ref "POWER") (pin "6") (pinfunction "6_6") (pintype "passive"))
      (node (ref "POWER") (pin "7") (pinfunction "7_7") (pintype "passive"))
      (node (ref "POWER") (pin "8") (pinfunction "8_8") (pintype "passive"))
      (node (ref "Q1") (pin "3") (pinfunction "E_3") (pintype "passive"))
      (node (ref "Q2") (pin "3") (pinfunction "E_3") (pintype "passive"))
      (node (ref "Q3") (pin "3") (pinfunction "E_3") (pintype "passive"))
      (node (ref "R10") (pin "2") (pinfunction "2_2") (pintype "passive"))
      (node (ref "R21") (pin "1") (pinfunction "1_1") (pintype "passive"))
      (node (ref "R23") (pin "1") (pinfunction "1_1") (pintype "passive"))
      (node (ref "R24") (pin "1") (pinfunction "1_1") (pintype "passive"))
      (node (ref "R25") (pin "1") (pinfunction "1_1") (pintype "passive"))
      (node (ref "R26") (pin "1") (pinfunction "1_1") (pintype "passive"))
      (node (ref "R3") (pin "2") (pinfunction "2_2") (pintype "passive"))
      (node (ref "R32") (pin "1") (pinfunction "1_1") (pintype "passive"))
      (node (ref "R4") (pin "2") (pinfunction "2_2") (pintype "passive"))
      (node (ref "R40") (pin "2") (pinfunction "2_2") (pintype "passive"))
      (node (ref "R47") (pin "2") (pinfunction "2_2") (pintype "passive"))
      (node (ref "R5") (pin "2") (pinfunction "2_2") (pintype "passive"))
      (node (ref "R55") (pin "2") (pinfunction "2_2") (pintype "passive"))
      (node (ref "R56") (pin "2") (pinfunction "2_2") (pintype "passive"))
      (node (ref "R57") (pin "2") (pinfunction "2_2") (pintype "passive"))
      (node (ref "R58") (pin "2") (pinfunction "2_2") (pintype "passive"))
      (node (ref "R59") (pin "1") (pinfunction "1_1") (pintype "passive"))
      (node (ref "R6") (pin "2") (pinfunction "2_2") (pintype "passive"))
      (node (ref "R7") (pin "2") (pinfunction "2_2") (pintype "passive"))
      (node (ref "RES") (pin "RING") (pinfunction "SLEEVE_RING") (pintype "bidirectional"))
      (node (ref "REV") (pin "RING") (pinfunction "SLEEVE_RING") (pintype "bidirectional"))
      (node (ref "RG1") (pin "2") (pinfunction "GND_2") (pintype "input"))
      (node (ref "SW1") (pin "3") (pinfunction "3_3") (pintype "passive"))
      (node (ref "SW3") (pin "P$1") (pinfunction "1_P$1") (pintype "bidirectional"))
      (node (ref "SW3") (pin "P$2") (pinfunction "2_P$2") (pintype "bidirectional"))
      (node (ref "SW4") (pin "P$1") (pinfunction "1_P$1") (pintype "bidirectional"))
      (node (ref "SW4") (pin "P$2") (pinfunction "2_P$2") (pintype "bidirectional"))
      (node (ref "SW5") (pin "P$1") (pinfunction "1_P$1") (pintype "bidirectional"))
      (node (ref "SW5") (pin "P$2") (pinfunction "2_P$2") (pintype "bidirectional"))
      (node (ref "SW6") (pin "P$1") (pinfunction "1_P$1") (pintype "bidirectional"))
      (node (ref "SW6") (pin "P$2") (pinfunction "2_P$2") (pintype "bidirectional"))
    )
    (net (code "61") (name "Net-(D1-PadA)") (class "Default")
      (node (ref "D1") (pin "A") (pinfunction "A_A") (pintype "passive"))
      (node (ref "R1") (pin "2") (pinfunction "2_2") (pintype "passive"))
    )
    (net (code "62") (name "Net-(D2-PadC)") (class "Default")
      (node (ref "D2") (pin "C") (pinfunction "C_C") (pintype "passive"))
      (node (ref "R2") (pin "2") (pinfunction "2_2") (pintype "passive"))
    )
    (net (code "63") (name "Net-(D3-A)") (class "Default")
      (node (ref "D3") (pin "ANODE") (pinfunction "A_ANODE") (pintype "passive"))
      (node (ref "IC1") (pin "3") (pinfunction "O_3") (pintype "output"))
    )
    (net (code "64") (name "Net-(D3-C)") (class "Default")
      (node (ref "D3") (pin "CATHODE") (pinfunction "C_CATHODE") (pintype "passive"))
      (node (ref "D4") (pin "CATHODE") (pinfunction "C_CATHODE") (pintype "passive"))
      (node (ref "R55") (pin "1") (pinfunction "1_1") (pintype "passive"))
      (node (ref "SW2") (pin "3") (pinfunction "3_3") (pintype "passive"))
    )
    (net (code "65") (name "Net-(D4-A)") (class "Default")
      (node (ref "D4") (pin "ANODE") (pinfunction "A_ANODE") (pintype "passive"))
      (node (ref "IC1") (pin "4") (pinfunction "O_4") (pintype "output"))
    )
    (net (code "66") (name "Net-(D5-C)") (class "Default")
      (node (ref "C7") (pin "1") (pinfunction "1_1") (pintype "passive"))
      (node (ref "D5") (pin "CATHODE") (pinfunction "C_CATHODE") (pintype "passive"))
      (node (ref "SW3") (pin "P$3") (pinfunction "3_P$3") (pintype "bidirectional"))
      (node (ref "SW3") (pin "P$4") (pinfunction "4_P$4") (pintype "bidirectional"))
    )
    (net (code "67") (name "Net-(D6-C)") (class "Default")
      (node (ref "C8") (pin "1") (pinfunction "1_1") (pintype "passive"))
      (node (ref "D6") (pin "CATHODE") (pinfunction "C_CATHODE") (pintype "passive"))
      (node (ref "SW4") (pin "P$3") (pinfunction "3_P$3") (pintype "bidirectional"))
      (node (ref "SW4") (pin "P$4") (pinfunction "4_P$4") (pintype "bidirectional"))
    )
    (net (code "68") (name "Net-(D7-C)") (class "Default")
      (node (ref "C9") (pin "1") (pinfunction "1_1") (pintype "passive"))
      (node (ref "D7") (pin "CATHODE") (pinfunction "C_CATHODE") (pintype "passive"))
      (node (ref "SW5") (pin "P$3") (pinfunction "3_P$3") (pintype "bidirectional"))
      (node (ref "SW5") (pin "P$4") (pinfunction "4_P$4") (pintype "bidirectional"))
    )
    (net (code "69") (name "Net-(D8-C)") (class "Default")
      (node (ref "C10") (pin "1") (pinfunction "1_1") (pintype "passive"))
      (node (ref "D8") (pin "CATHODE") (pinfunction "C_CATHODE") (pintype "passive"))
      (node (ref "SW6") (pin "P$3") (pinfunction "3_P$3") (pintype "bidirectional"))
      (node (ref "SW6") (pin "P$4") (pinfunction "4_P$4") (pintype "bidirectional"))
    )
    (net (code "70") (name "Net-(D9-A)") (class "Default")
      (node (ref "D9") (pin "ANODE") (pinfunction "A_ANODE") (pintype "passive"))
      (node (ref "IC3") (pin "6") (pinfunction "O_6") (pintype "output"))
    )
    (net (code "71") (name "Net-(D10-A)") (class "Default")
      (node (ref "D10") (pin "ANODE") (pinfunction "A_ANODE") (pintype "passive"))
      (node (ref "IC3") (pin "4") (pinfunction "O_4") (pintype "output"))
      (node (ref "IC5") (pin "10") (pinfunction "U/~{D}_10") (pintype "input"))
    )
    (net (code "72") (name "Net-(D10-C)") (class "Default")
      (node (ref "D10") (pin "CATHODE") (pinfunction "C_CATHODE") (pintype "passive"))
      (node (ref "D9") (pin "CATHODE") (pinfunction "C_CATHODE") (pintype "passive"))
      (node (ref "R21") (pin "2") (pinfunction "2_2") (pintype "passive"))
      (node (ref "R22") (pin "2") (pinfunction "2_2") (pintype "passive"))
    )
    (net (code "73") (name "Net-(D11-A)") (class "Default")
      (node (ref "D11") (pin "ANODE") (pinfunction "A_ANODE") (pintype "passive"))
      (node (ref "IC4") (pin "6") (pinfunction "-IN_6") (pintype "input"))
      (node (ref "R27") (pin "1") (pinfunction "1_1") (pintype "passive"))
    )
    (net (code "74") (name "Net-(D11-C)") (class "Default")
      (node (ref "D11") (pin "CATHODE") (pinfunction "C_CATHODE") (pintype "passive"))
      (node (ref "IC4") (pin "7") (pinfunction "OUT_7") (pintype "output"))
    )
    (net (code "75") (name "Net-(D12-A)") (class "Default")
      (node (ref "D12") (pin "ANODE") (pinfunction "A_ANODE") (pintype "passive"))
      (node (ref "R20") (pin "2") (pinfunction "2_2") (pintype "passive"))
      (node (ref "R52") (pin "1") (pinfunction "1_1") (pintype "passive"))
    )
    (net (code "76") (name "Net-(D12-C)") (class "Default")
      (node (ref "D12") (pin "CATHODE") (pinfunction "C_CATHODE") (pintype "passive"))
      (node (ref "IC4") (pin "1") (pinfunction "OUT_1") (pintype "output"))
    )
    (net (code "77") (name "Net-(D13-A)") (class "Default")
      (node (ref "D13") (pin "ANODE") (pinfunction "A_ANODE") (pintype "passive"))
      (node (ref "IC8") (pin "2") (pinfunction "OUT_2") (pintype "output"))
      (node (ref "R41") (pin "2") (pinfunction "2_2") (pintype "passive"))
      (node (ref "R44") (pin "1") (pinfunction "1_1") (pintype "passive"))
    )
    (net (code "78") (name "Net-(D14-A)") (class "Default")
      (node (ref "D14") (pin "ANODE") (pinfunction "A_ANODE") (pintype "passive"))
      (node (ref "IC8") (pin "13") (pinfunction "OUT_13") (pintype "output"))
      (node (ref "IC8") (pin "14") (pinfunction "OUT_14") (pintype "output"))
      (node (ref "R43") (pin "2") (pinfunction "2_2") (pintype "passive"))
      (node (ref "R46") (pin "1") (pinfunction "1_1") (pintype "passive"))
    )
    (net (code "79") (name "Net-(HLD-PadTIP)") (class "Default")
      (node (ref "HLD") (pin "TIP") (pinfunction "TIP_TIP") (pintype "bidirectional"))
      (node (ref "R11") (pin "1") (pinfunction "1_1") (pintype "passive"))
      (node (ref "R7") (pin "1") (pinfunction "1_1") (pintype "passive"))
    )
    (net (code "80") (name "Net-(IC2A-I)") (class "Default")
      (node (ref "IC2") (pin "1") (pinfunction "I_1") (pintype "input"))
      (node (ref "R11") (pin "2") (pinfunction "2_2") (pintype "passive"))
    )
    (net (code "81") (name "Net-(IC2A-O)") (class "Default")
      (node (ref "IC2") (pin "2") (pinfunction "O_2") (pintype "output"))
      (node (ref "R15") (pin "1") (pinfunction "1_1") (pintype "passive"))
    )
    (net (code "82") (name "Net-(IC2B-I)") (class "Default")
      (node (ref "IC2") (pin "3") (pinfunction "I_3") (pintype "input"))
      (node (ref "R12") (pin "2") (pinfunction "2_2") (pintype "passive"))
    )
    (net (code "83") (name "Net-(IC2B-O)") (class "Default")
      (node (ref "IC2") (pin "4") (pinfunction "O_4") (pintype "output"))
      (node (ref "R16") (pin "1") (pinfunction "1_1") (pintype "passive"))
    )
    (net (code "84") (name "Net-(IC2C-I)") (class "Default")
      (node (ref "IC2") (pin "5") (pinfunction "I_5") (pintype "input"))
      (node (ref "R13") (pin "2") (pinfunction "2_2") (pintype "passive"))
    )
    (net (code "85") (name "Net-(IC2C-O)") (class "Default")
      (node (ref "IC2") (pin "6") (pinfunction "O_6") (pintype "output"))
      (node (ref "R17") (pin "1") (pinfunction "1_1") (pintype "passive"))
    )
    (net (code "86") (name "Net-(IC2D-I)") (class "Default")
      (node (ref "IC2") (pin "9") (pinfunction "I_9") (pintype "input"))
      (node (ref "R14") (pin "2") (pinfunction "2_2") (pintype "passive"))
    )
    (net (code "87") (name "Net-(IC2D-O)") (class "Default")
      (node (ref "IC2") (pin "8") (pinfunction "O_8") (pintype "output"))
      (node (ref "R18") (pin "1") (pinfunction "1_1") (pintype "passive"))
    )
    (net (code "88") (name "Net-(IC2E-O)") (class "Default")
      (node (ref "IC2") (pin "10") (pinfunction "O_10") (pintype "output"))
      (node (ref "L1") (pin "A") (pinfunction "A_A") (pintype "passive"))
    )
    (net (code "89") (name "Net-(IC3A-O)") (class "Default")
      (node (ref "IC3") (pin "2") (pinfunction "O_2") (pintype "output"))
      (node (ref "IC5") (pin "5") (pinfunction "CIN_5") (pintype "input"))
    )
    (net (code "90") (name "Net-(IC3D-O)") (class "Default")
      (node (ref "IC3") (pin "8") (pinfunction "O_8") (pintype "output"))
      (node (ref "IC5") (pin "9") (pinfunction "RES_9") (pintype "input"))
    )
    (net (code "91") (name "Net-(IC4A--IN)") (class "Default")
      (node (ref "IC4") (pin "2") (pinfunction "-IN_2") (pintype "input"))
      (node (ref "R20") (pin "1") (pinfunction "1_1") (pintype "passive"))
      (node (ref "R8") (pin "1") (pinfunction "1_1") (pintype "passive"))
      (node (ref "R9") (pin "1") (pinfunction "1_1") (pintype "passive"))
    )
    (net (code "92") (name "Net-(IC4B-+IN)") (class "Default")
      (node (ref "IC4") (pin "12") (pinfunction "+IN_12") (pintype "input"))
      (node (ref "IC4") (pin "5") (pinfunction "+IN_5") (pintype "input"))
      (node (ref "R19") (pin "2") (pinfunction "2_2") (pintype "passive"))
    )
    (net (code "93") (name "Net-(IC4C--IN)") (class "Default")
      (node (ref "IC4") (pin "9") (pinfunction "-IN_9") (pintype "input"))
      (node (ref "R27") (pin "2") (pinfunction "2_2") (pintype "passive"))
      (node (ref "R28") (pin "1") (pinfunction "1_1") (pintype "passive"))
      (node (ref "R52") (pin "2") (pinfunction "2_2") (pintype "passive"))
    )
    (net (code "94") (name "Net-(IC4C-OUT)") (class "Default")
      (node (ref "IC4") (pin "8") (pinfunction "OUT_8") (pintype "output"))
      (node (ref "R28") (pin "2") (pinfunction "2_2") (pintype "passive"))
      (node (ref "R29") (pin "1") (pinfunction "1_1") (pintype "passive"))
      (node (ref "R30") (pin "1") (pinfunction "1_1") (pintype "passive"))
      (node (ref "R31") (pin "1") (pinfunction "1_1") (pintype "passive"))
    )
    (net (code "95") (name "Net-(IC4D--IN)") (class "Default")
      (node (ref "IC4") (pin "13") (pinfunction "-IN_13") (pintype "input"))
      (node (ref "IC4") (pin "14") (pinfunction "OUT_14") (pintype "output"))
      (node (ref "R8") (pin "2") (pinfunction "2_2") (pintype "passive"))
    )
    (net (code "96") (name "Net-(IC5A-CLK)") (class "Default")
      (node (ref "C11") (pin "1") (pinfunction "1_1") (pintype "passive"))
      (node (ref "IC5") (pin "15") (pinfunction "CLK_15") (pintype "input"))
      (node (ref "R22") (pin "1") (pinfunction "1_1") (pintype "passive"))
    )
    (net (code "97") (name "Net-(IC5A-Q0)") (class "Default")
      (node (ref "IC5") (pin "6") (pinfunction "Q0_6") (pintype "output"))
      (node (ref "IC6") (pin "1") (pinfunction "A0_1") (pintype "input"))
      (node (ref "IC7") (pin "1") (pinfunction "A0_1") (pintype "input"))
      (node (ref "IC9") (pin "10") (pinfunction "A_10") (pintype "input"))
    )
    (net (code "98") (name "Net-(IC5A-Q1)") (class "Default")
      (node (ref "IC5") (pin "11") (pinfunction "Q1_11") (pintype "output"))
      (node (ref "IC6") (pin "16") (pinfunction "A1_16") (pintype "input"))
      (node (ref "IC7") (pin "16") (pinfunction "A1_16") (pintype "input"))
      (node (ref "IC9") (pin "9") (pinfunction "B_9") (pintype "input"))
    )
    (net (code "99") (name "Net-(IC6-DA)") (class "Default")
      (node (ref "IC6") (pin "8") (pinfunction "DA_8") (pintype "passive"))
      (node (ref "R33") (pin "1") (pinfunction "1_1") (pintype "passive"))
    )
    (net (code "100") (name "Net-(IC6-DB)") (class "Default")
      (node (ref "IC6") (pin "9") (pinfunction "DB_9") (pintype "passive"))
      (node (ref "R34") (pin "1") (pinfunction "1_1") (pintype "passive"))
    )
    (net (code "101") (name "Net-(IC6-S1A)") (class "Default")
      (node (ref "IC6") (pin "10") (pinfunction "S4B_10") (pintype "passive"))
      (node (ref "IC6") (pin "4") (pinfunction "S1A_4") (pintype "passive"))
      (node (ref "IC7") (pin "12") (pinfunction "S2B_12") (pintype "passive"))
      (node (ref "IC7") (pin "6") (pinfunction "S3A_6") (pintype "passive"))
      (node (ref "R23") (pin "2") (pinfunction "2_2") (pintype "passive"))
      (node (ref "R48") (pin "2") (pinfunction "2_2") (pintype "passive"))
    )
    (net (code "102") (name "Net-(IC6-S1B)") (class "Default")
      (node (ref "IC6") (pin "13") (pinfunction "S1B_13") (pintype "passive"))
      (node (ref "IC6") (pin "5") (pinfunction "S2A_5") (pintype "passive"))
      (node (ref "IC7") (pin "11") (pinfunction "S3B_11") (pintype "passive"))
      (node (ref "IC7") (pin "7") (pinfunction "S4A_7") (pintype "passive"))
      (node (ref "R24") (pin "2") (pinfunction "2_2") (pintype "passive"))
      (node (ref "R49") (pin "2") (pinfunction "2_2") (pintype "passive"))
    )
    (net (code "103") (name "Net-(IC6-S2B)") (class "Default")
      (node (ref "IC6") (pin "12") (pinfunction "S2B_12") (pintype "passive"))
      (node (ref "IC6") (pin "6") (pinfunction "S3A_6") (pintype "passive"))
      (node (ref "IC7") (pin "10") (pinfunction "S4B_10") (pintype "passive"))
      (node (ref "IC7") (pin "4") (pinfunction "S1A_4") (pintype "passive"))
      (node (ref "R25") (pin "2") (pinfunction "2_2") (pintype "passive"))
      (node (ref "R50") (pin "2") (pinfunction "2_2") (pintype "passive"))
    )
    (net (code "104") (name "Net-(IC6-S3B)") (class "Default")
      (node (ref "IC6") (pin "11") (pinfunction "S3B_11") (pintype "passive"))
      (node (ref "IC6") (pin "7") (pinfunction "S4A_7") (pintype "passive"))
      (node (ref "IC7") (pin "13") (pinfunction "S1B_13") (pintype "passive"))
      (node (ref "IC7") (pin "5") (pinfunction "S2A_5") (pintype "passive"))
      (node (ref "R26") (pin "2") (pinfunction "2_2") (pintype "passive"))
      (node (ref "R51") (pin "2") (pinfunction "2_2") (pintype "passive"))
    )
    (net (code "105") (name "Net-(IC7-DA)") (class "Default")
      (node (ref "IC7") (pin "8") (pinfunction "DA_8") (pintype "passive"))
      (node (ref "R35") (pin "1") (pinfunction "1_1") (pintype "passive"))
    )
    (net (code "106") (name "Net-(IC7-DB)") (class "Default")
      (node (ref "IC7") (pin "9") (pinfunction "DB_9") (pintype "passive"))
      (node (ref "R36") (pin "1") (pinfunction "1_1") (pintype "passive"))
    )
    (net (code "107") (name "Net-(IC8A-+IN)") (class "Default")
      (node (ref "IC8") (pin "5") (pinfunction "+IN_5") (pintype "input"))
      (node (ref "R29") (pin "2") (pinfunction "2_2") (pintype "passive"))
      (node (ref "R41") (pin "1") (pinfunction "1_1") (pintype "passive"))
    )
    (net (code "108") (name "Net-(IC8A--IN)") (class "Default")
      (node (ref "IC8") (pin "4") (pinfunction "-IN_4") (pintype "input"))
      (node (ref "R37") (pin "2") (pinfunction "2_2") (pintype "passive"))
      (node (ref "R38") (pin "1") (pinfunction "1_1") (pintype "passive"))
    )
    (net (code "109") (name "Net-(IC8B-+IN)") (class "Default")
      (node (ref "IC8") (pin "7") (pinfunction "+IN_7") (pintype "input"))
      (node (ref "R30") (pin "2") (pinfunction "2_2") (pintype "passive"))
      (node (ref "R42") (pin "1") (pinfunction "1_1") (pintype "passive"))
    )
    (net (code "110") (name "Net-(IC8B--IN)") (class "Default")
      (node (ref "IC8") (pin "6") (pinfunction "-IN_6") (pintype "input"))
      (node (ref "R38") (pin "2") (pinfunction "2_2") (pintype "passive"))
      (node (ref "R39") (pin "1") (pinfunction "1_1") (pintype "passive"))
    )
    (net (code "111") (name "Net-(IC8C-+IN)") (class "Default")
      (node (ref "IC8") (pin "9") (pinfunction "+IN_9") (pintype "input"))
      (node (ref "R31") (pin "2") (pinfunction "2_2") (pintype "passive"))
      (node (ref "R43") (pin "1") (pinfunction "1_1") (pintype "passive"))
    )
    (net (code "112") (name "Net-(IC8C--IN)") (class "Default")
      (node (ref "IC8") (pin "11") (pinfunction "+IN_11") (pintype "input"))
      (node (ref "IC8") (pin "8") (pinfunction "-IN_8") (pintype "input"))
      (node (ref "R39") (pin "2") (pinfunction "2_2") (pintype "passive"))
      (node (ref "R40") (pin "1") (pinfunction "1_1") (pintype "passive"))
    )
    (net (code "113") (name "Net-(L1-C)") (class "Default")
      (node (ref "L1") (pin "K") (pinfunction "C_K") (pintype "passive"))
      (node (ref "R3") (pin "1") (pinfunction "1_1") (pintype "passive"))
    )
    (net (code "114") (name "Net-(L2-C)") (class "Default")
      (node (ref "L2") (pin "K") (pinfunction "C_K") (pintype "passive"))
      (node (ref "R4") (pin "1") (pinfunction "1_1") (pintype "passive"))
    )
    (net (code "115") (name "Net-(L3-C)") (class "Default")
      (node (ref "L3") (pin "K") (pinfunction "C_K") (pintype "passive"))
      (node (ref "R5") (pin "1") (pinfunction "1_1") (pintype "passive"))
    )
    (net (code "116") (name "Net-(L4-C)") (class "Default")
      (node (ref "L4") (pin "K") (pinfunction "C_K") (pintype "passive"))
      (node (ref "R6") (pin "1") (pinfunction "1_1") (pintype "passive"))
    )
    (net (code "117") (name "Net-(L5-C)") (class "Default")
      (node (ref "L5") (pin "K") (pinfunction "C_K") (pintype "passive"))
      (node (ref "L6") (pin "K") (pinfunction "C_K") (pintype "passive"))
      (node (ref "L7") (pin "K") (pinfunction "C_K") (pintype "passive"))
      (node (ref "L8") (pin "K") (pinfunction "C_K") (pintype "passive"))
      (node (ref "R32") (pin "2") (pinfunction "2_2") (pintype "passive"))
    )
    (net (code "118") (name "Net-(POWER-Pad1)") (class "Default")
      (node (ref "POWER") (pin "1") (pinfunction "1_1") (pintype "passive"))
      (node (ref "POWER") (pin "2") (pinfunction "2_2") (pintype "passive"))
      (node (ref "R2") (pin "1") (pinfunction "1_1") (pintype "passive"))
    )
    (net (code "119") (name "Net-(POWER-Pad10)") (class "Default")
      (node (ref "POWER") (pin "10") (pinfunction "10_10") (pintype "passive"))
      (node (ref "POWER") (pin "9") (pinfunction "9_9") (pintype "passive"))
      (node (ref "R1") (pin "1") (pinfunction "1_1") (pintype "passive"))
    )
    (net (code "120") (name "Net-(Q3-C)") (class "Default")
      (node (ref "Q3") (pin "2") (pinfunction "C_2") (pintype "passive"))
      (node (ref "R54") (pin "1") (pinfunction "1_1") (pintype "passive"))
      (node (ref "SW2") (pin "1") (pinfunction "1_1") (pintype "passive"))
    )
    (net (code "121") (name "Net-(R10-Pad1)") (class "Default")
      (node (ref "R10") (pin "1") (pinfunction "1_1") (pintype "passive"))
      (node (ref "R14") (pin "1") (pinfunction "1_1") (pintype "passive"))
      (node (ref "RES") (pin "TIP") (pinfunction "TIP_TIP") (pintype "bidirectional"))
    )
    (net (code "122") (name "unconnected-(FWD-SHUNT-PadNORMAL)") (class "Default")
      (node (ref "FWD") (pin "NORMAL") (pinfunction "SHUNT_NORMAL") (pintype "bidirectional"))
    )
    (net (code "123") (name "unconnected-(HLD-SHUNT-PadNORMAL)") (class "Default")
      (node (ref "HLD") (pin "NORMAL") (pinfunction "SHUNT_NORMAL") (pintype "bidirectional"))
    )
    (net (code "124") (name "unconnected-(I/O1-SHUNT-PadNORMAL)") (class "Default")
      (node (ref "I/O1") (pin "NORMAL") (pinfunction "SHUNT_NORMAL") (pintype "bidirectional"))
    )
    (net (code "125") (name "unconnected-(I/O2-SHUNT-PadNORMAL)") (class "Default")
      (node (ref "I/O2") (pin "NORMAL") (pinfunction "SHUNT_NORMAL") (pintype "bidirectional"))
    )
    (net (code "126") (name "unconnected-(I/O3-SHUNT-PadNORMAL)") (class "Default")
      (node (ref "I/O3") (pin "NORMAL") (pinfunction "SHUNT_NORMAL") (pintype "bidirectional"))
    )
    (net (code "127") (name "unconnected-(I/O4-SHUNT-PadNORMAL)") (class "Default")
      (node (ref "I/O4") (pin "NORMAL") (pinfunction "SHUNT_NORMAL") (pintype "bidirectional"))
    )
    (net (code "128") (name "unconnected-(IC5A-CO-Pad7)") (class "Default")
      (node (ref "IC5") (pin "7") (pinfunction "CO_7") (pintype "output"))
    )
    (net (code "129") (name "unconnected-(IC5A-Q2-Pad14)") (class "Default")
      (node (ref "IC5") (pin "14") (pinfunction "Q2_14") (pintype "output"))
    )
    (net (code "130") (name "unconnected-(IC5A-Q3-Pad2)") (class "Default")
      (node (ref "IC5") (pin "2") (pinfunction "Q3_2") (pintype "output"))
    )
    (net (code "131") (name "unconnected-(IC9A-Y0-Pad1)") (class "Default")
      (node (ref "IC9") (pin "1") (pinfunction "Y0_1") (pintype "bidirectional"))
    )
    (net (code "132") (name "unconnected-(IC9A-Y1-Pad5)") (class "Default")
      (node (ref "IC9") (pin "5") (pinfunction "Y1_5") (pintype "bidirectional"))
    )
    (net (code "133") (name "unconnected-(IC9A-Y2-Pad2)") (class "Default")
      (node (ref "IC9") (pin "2") (pinfunction "Y2_2") (pintype "bidirectional"))
    )
    (net (code "134") (name "unconnected-(IC9A-Y3-Pad4)") (class "Default")
      (node (ref "IC9") (pin "4") (pinfunction "Y3_4") (pintype "bidirectional"))
    )
    (net (code "135") (name "unconnected-(IC10A-Q2-Pad10)") (class "Default")
      (node (ref "IC10") (pin "10") (pinfunction "Q2_10") (pintype "output"))
    )
    (net (code "136") (name "unconnected-(IC10A-Q3-Pad1)") (class "Default")
      (node (ref "IC10") (pin "1") (pinfunction "Q3_1") (pintype "output"))
    )
    (net (code "137") (name "unconnected-(O/I1-SHUNT-PadNORMAL)") (class "Default")
      (node (ref "O/I1") (pin "NORMAL") (pinfunction "SHUNT_NORMAL") (pintype "bidirectional"))
    )
    (net (code "138") (name "unconnected-(O/I2-SHUNT-PadNORMAL)") (class "Default")
      (node (ref "O/I2") (pin "NORMAL") (pinfunction "SHUNT_NORMAL") (pintype "bidirectional"))
    )
    (net (code "139") (name "unconnected-(O/I3-SHUNT-PadNORMAL)") (class "Default")
      (node (ref "O/I3") (pin "NORMAL") (pinfunction "SHUNT_NORMAL") (pintype "bidirectional"))
    )
    (net (code "140") (name "unconnected-(O/I4-SHUNT-PadNORMAL)") (class "Default")
      (node (ref "O/I4") (pin "NORMAL") (pinfunction "SHUNT_NORMAL") (pintype "bidirectional"))
    )
    (net (code "141") (name "unconnected-(RES-SHUNT-PadNORMAL)") (class "Default")
      (node (ref "RES") (pin "NORMAL") (pinfunction "SHUNT_NORMAL") (pintype "bidirectional"))
    )
    (net (code "142") (name "unconnected-(REV-SHUNT-PadNORMAL)") (class "Default")
      (node (ref "REV") (pin "NORMAL") (pinfunction "SHUNT_NORMAL") (pintype "bidirectional"))
    )
  )
)
